# buckboost.net
KiCad netlist of a schematic drawn in Altium Designer
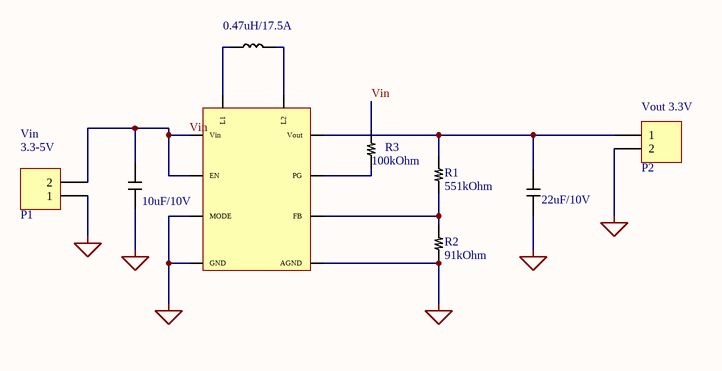
[diagram p0: buckboost.SchDoc]

(export (version "E")
  (design (tool "Eeschema 10.0.6"))
  (components
    (comp (ref "*") (value "TPS63802") (footprint "TPS63802") (libsource (lib "Schlib1") (part "TPS63802")))
    (comp (ref "C1") (value "10uF/10V") (footprint "cap") (libsource (lib "Schlib1") (part "cap")))
    (comp (ref "C2") (value "22uF/10V") (footprint "cap") (libsource (lib "Schlib1") (part "cap")))
    (comp (ref "L") (value "0.47uH/17.5A") (footprint "coil") (libsource (lib "Schlib1") (part "coil")))
    (comp (ref "P1")
      (value "Domino 2")
      (footprint "DOMINO SMALL 2")
      (description "Domino, 2-Pin")
      (fields (field (name "PUBLISHER") "Altium Limited"))
      (libsource (lib "PIF_Library") (part "Domino 2"))
    )
    (comp (ref "P2")
      (value "Domino 2")
      (footprint "DOMINO SMALL 2")
      (description "Domino, 2-Pin")
      (fields (field (name "PUBLISHER") "Altium Limited"))
      (libsource (lib "") (part "Domino 2_1"))
    )
    (comp (ref "R1") (value "551kOhm") (footprint "resistor") (libsource (lib "Schlib1") (part "resistor")))
    (comp (ref "R2") (value "91kOhm") (footprint "resistor") (libsource (lib "Schlib1") (part "resistor")))
    (comp (ref "R3") (value "100kOhm") (footprint "resistor") (libsource (lib "Schlib1") (part "resistor")))
  )
  (nets
    (net (code "1") (name "/Vin") (class "Default")
      (node (ref "*") (pin "1") (pinfunction "EN_1") (pintype "passive"))
      (node (ref "*") (pin "10") (pinfunction "Vin_10") (pintype "passive"))
      (node (ref "C1") (pin "1") (pinfunction "1_1") (pintype "passive"))
      (node (ref "P1") (pin "2") (pinfunction "2_2") (pintype "passive"))
      (node (ref "R3") (pin "2") (pinfunction "2_2") (pintype "passive"))
    )
    (net (code "2") (name "GND") (class "Default")
      (node (ref "*") (pin "2") (pinfunction "MODE_2") (pintype "passive"))
      (node (ref "*") (pin "3") (pinfunction "AGND_3") (pintype "passive"))
      (node (ref "*") (pin "8") (pinfunction "GND_8") (pintype "passive"))
      (node (ref "C1") (pin "2") (pinfunction "2_2") (pintype "passive"))
      (node (ref "C2") (pin "1") (pinfunction "1_1") (pintype "passive"))
      (node (ref "P1") (pin "1") (pinfunction "1_1") (pintype "passive"))
      (node (ref "P2") (pin "2") (pinfunction "2_2") (pintype "passive"))
      (node (ref "R2") (pin "1") (pinfunction "1_1") (pintype "passive"))
    )
    (net (code "3") (name "Net-(*-FB)") (class "Default")
      (node (ref "*") (pin "4") (pinfunction "FB_4") (pintype "passive"))
      (node (ref "R1") (pin "2") (pinfunction "2_2") (pintype "passive"))
      (node (ref "R2") (pin "2") (pinfunction "2_2") (pintype "passive"))
    )
    (net (code "4") (name "Net-(*-L1)") (class "Default")
      (node (ref "*") (pin "9") (pinfunction "L1_9") (pintype "passive"))
      (node (ref "L") (pin "1") (pinfunction "1_1") (pintype "passive"))
    )
    (net (code "5") (name "Net-(*-L2)") (class "Default")
      (node (ref "*") (pin "7") (pinfunction "L2_7") (pintype "passive"))
      (node (ref "L") (pin "2") (pinfunction "2_2") (pintype "passive"))
    )
    (net (code "6") (name "Net-(*-PG)") (class "Default")
      (node (ref "*") (pin "5") (pinfunction "PG_5") (pintype "passive"))
      (node (ref "R3") (pin "1") (pinfunction "1_1") (pintype "passive"))
    )
    (net (code "7") (name "Net-(*-Vout)") (class "Default")
      (node (ref "*") (pin "6") (pinfunction "Vout_6") (pintype "passive"))
      (node (ref "C2") (pin "2") (pinfunction "2_2") (pintype "passive"))
      (node (ref "P2") (pin "1") (pinfunction "1_1") (pintype "passive"))
      (node (ref "R1") (pin "1") (pinfunction "1_1") (pintype "passive"))
    )
  )
)
